# heater_control.net
KiCad netlist of a schematic drawn in Altium Designer
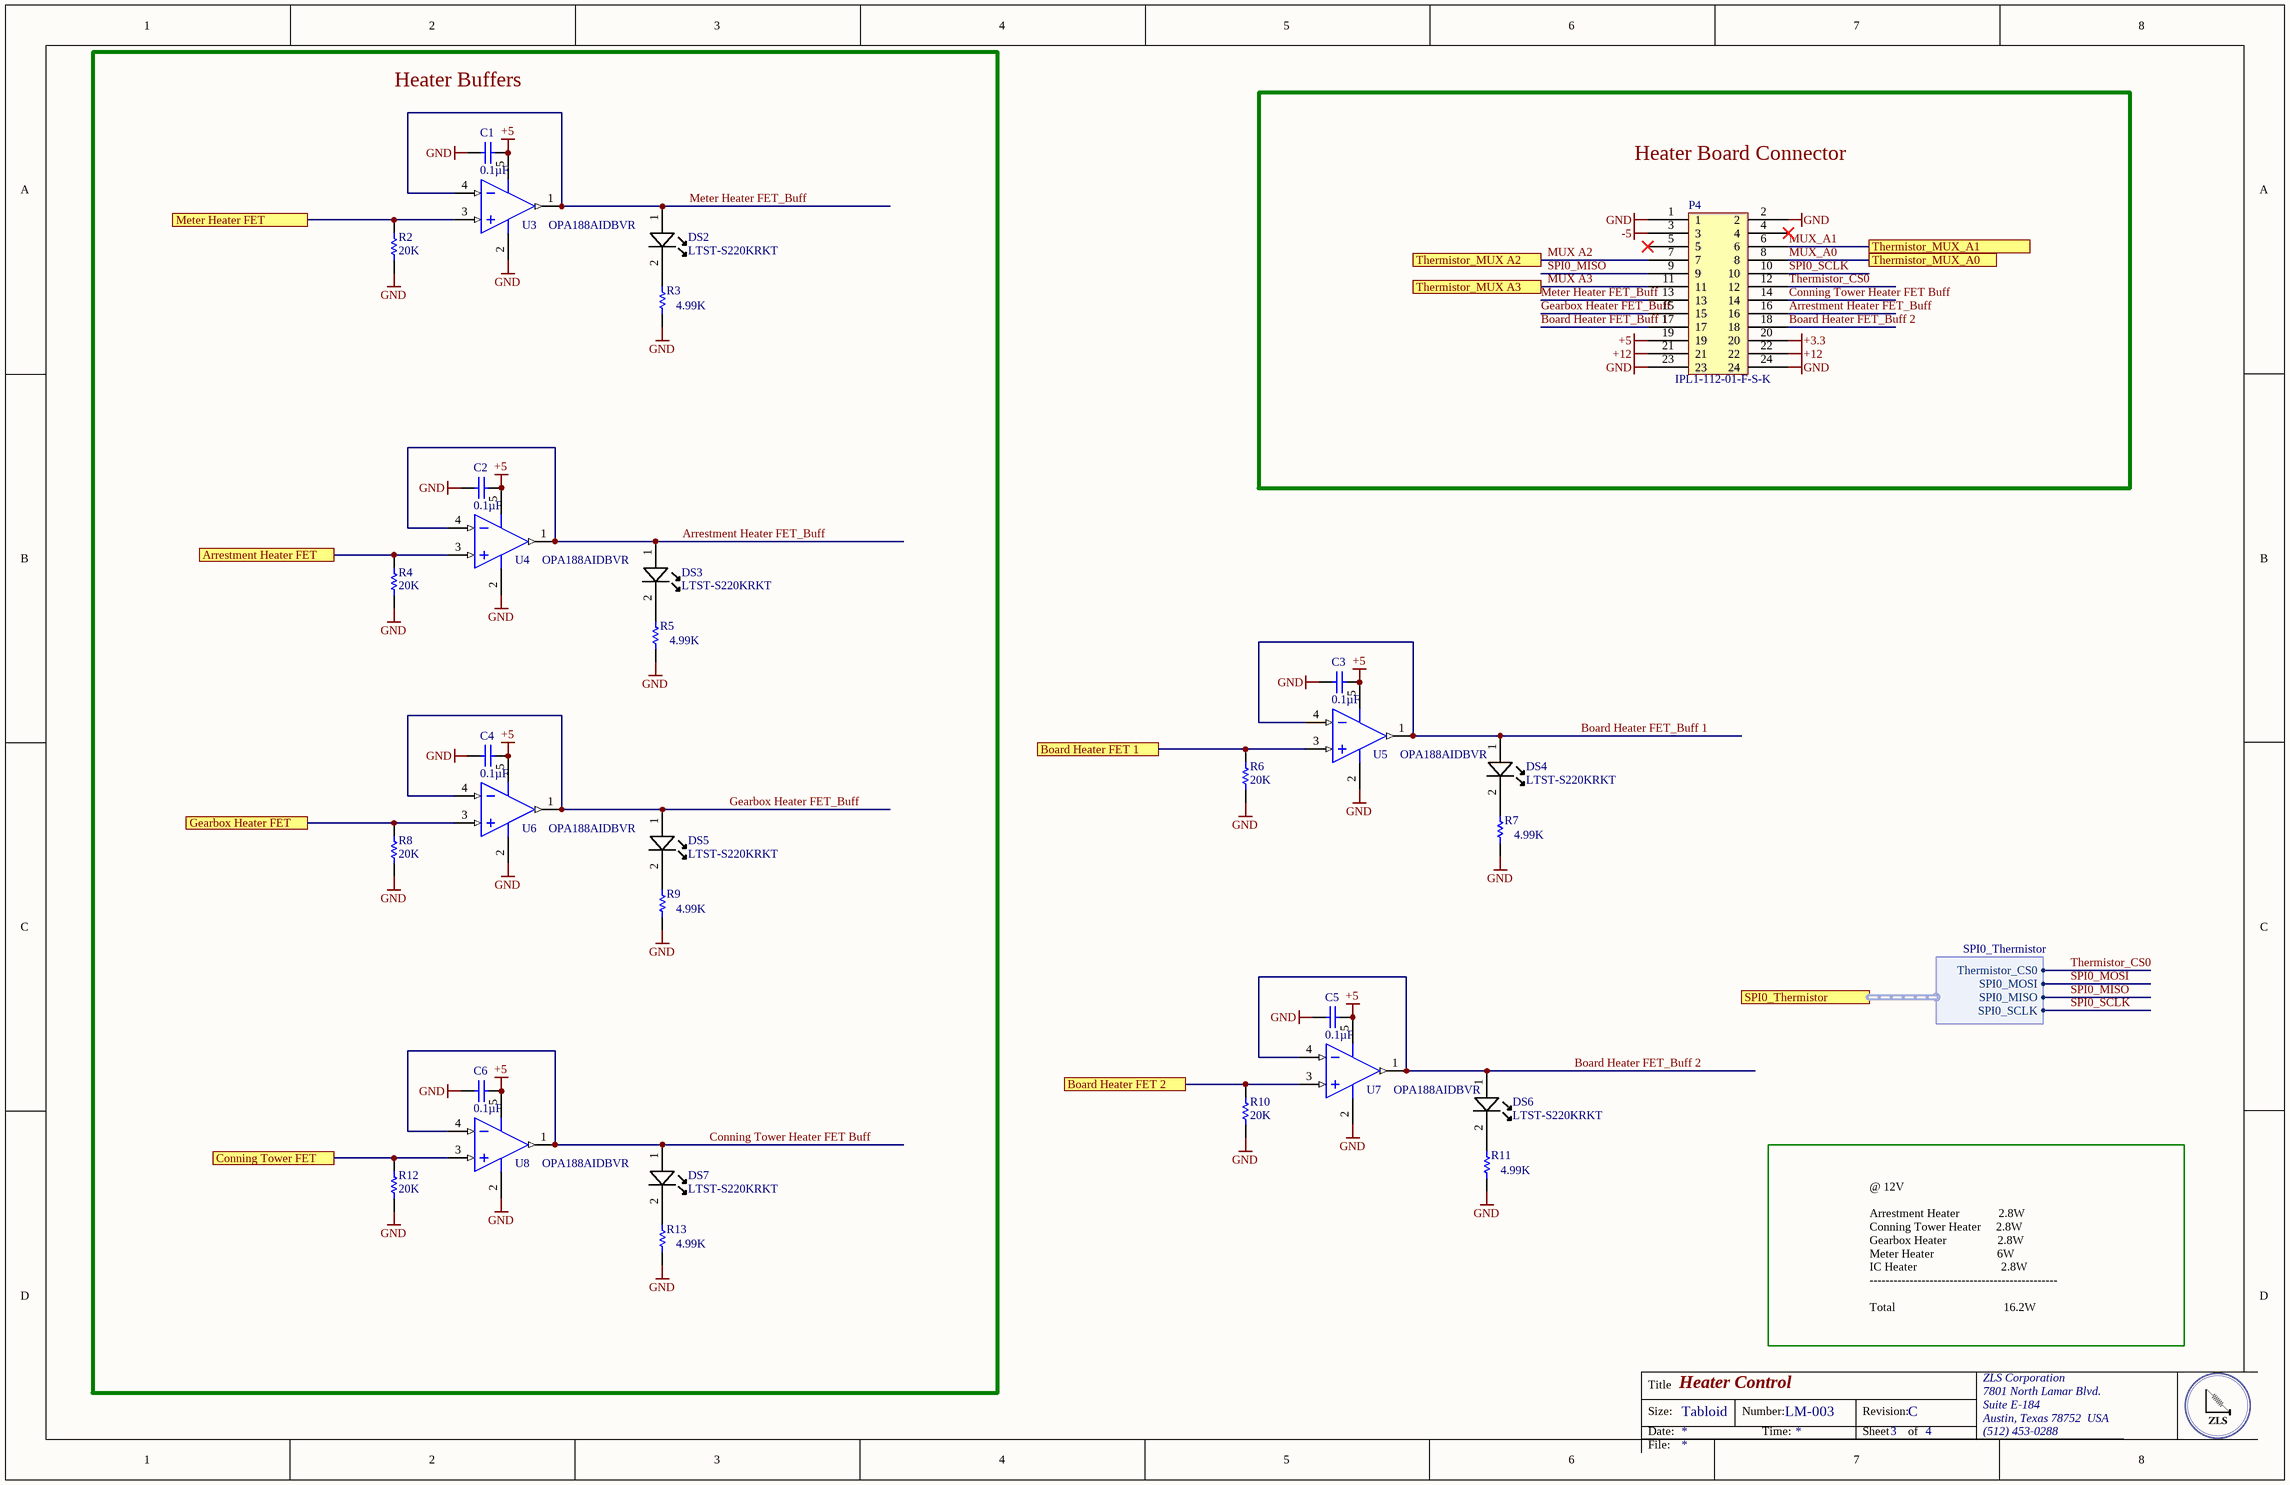
[diagram p0: heater_control.SchDoc]

(export (version "E")
  (design (tool "Eeschema 10.0.6"))
  (components
    (comp (ref "C1")
      (value "CAP CER 0.1UF 25V X7R 0805")
      (footprint "CAPC0805(2012)145_N")
      (fields
        (field (name "MANUFACTURER") "Murata Electronics North America")
        (field (name "MANUFACTURER PART NUMBER") "GRM21BR71E104KA01L")
        (field (name "CAPACITANCE") "0.1µF")
        (field (name "TOLERANCE") "±10%")
      )
      (libsource (lib "Altium Content Vault") (part "CMP-1036-04795-1"))
    )
    (comp (ref "C2")
      (value "CAP CER 0.1UF 25V X7R 0805")
      (footprint "CAPC0805(2012)145_N")
      (fields
        (field (name "MANUFACTURER") "Murata Electronics North America")
        (field (name "MANUFACTURER PART NUMBER") "GRM21BR71E104KA01L")
        (field (name "CAPACITANCE") "0.1µF")
        (field (name "TOLERANCE") "±10%")
      )
      (libsource (lib "Altium Content Vault") (part "CMP-1036-04795-1"))
    )
    (comp (ref "C3")
      (value "CAP CER 0.1UF 25V X7R 0805")
      (footprint "CAPC0805(2012)145_N")
      (fields
        (field (name "MANUFACTURER") "Murata Electronics North America")
        (field (name "MANUFACTURER PART NUMBER") "GRM21BR71E104KA01L")
        (field (name "CAPACITANCE") "0.1µF")
        (field (name "TOLERANCE") "±10%")
      )
      (libsource (lib "Altium Content Vault") (part "CMP-1036-04795-1"))
    )
    (comp (ref "C4")
      (value "CAP CER 0.1UF 25V X7R 0805")
      (footprint "CAPC0805(2012)145_N")
      (fields
        (field (name "MANUFACTURER") "Murata Electronics North America")
        (field (name "MANUFACTURER PART NUMBER") "GRM21BR71E104KA01L")
        (field (name "CAPACITANCE") "0.1µF")
        (field (name "TOLERANCE") "±10%")
      )
      (libsource (lib "Altium Content Vault") (part "CMP-1036-04795-1"))
    )
    (comp (ref "C5")
      (value "CAP CER 0.1UF 25V X7R 0805")
      (footprint "CAPC0805(2012)145_N")
      (fields
        (field (name "MANUFACTURER") "Murata Electronics North America")
        (field (name "MANUFACTURER PART NUMBER") "GRM21BR71E104KA01L")
        (field (name "CAPACITANCE") "0.1µF")
        (field (name "TOLERANCE") "±10%")
      )
      (libsource (lib "Altium Content Vault") (part "CMP-1036-04795-1"))
    )
    (comp (ref "C6")
      (value "CAP CER 0.1UF 25V X7R 0805")
      (footprint "CAPC0805(2012)145_N")
      (fields
        (field (name "MANUFACTURER") "Murata Electronics North America")
        (field (name "MANUFACTURER PART NUMBER") "GRM21BR71E104KA01L")
        (field (name "CAPACITANCE") "0.1µF")
        (field (name "TOLERANCE") "±10%")
      )
      (libsource (lib "Altium Content Vault") (part "CMP-1036-04795-1"))
    )
    (comp (ref "DS2")
      (value "Visible Name Value Type    False Description Lite-On LTST-S220KRKT Red LED, 631 nm 2012 (0805) Side View, Rectangle Lens SMD package STRING")
      (footprint "0805C_L")
      (fields
        (field (name "MANUFACTURER") "Vishay / Lite-On")
        (field (name "MANUFACTURER PART NUMBER") "LTST-S220KRKT")
      )
      (libsource (lib "*") (part "LED A/K"))
    )
    (comp (ref "DS3")
      (value "Visible Name Value Type    False Description Lite-On LTST-S220KRKT Red LED, 631 nm 2012 (0805) Side View, Rectangle Lens SMD package STRING")
      (footprint "0805C_L")
      (fields
        (field (name "MANUFACTURER") "Vishay / Lite-On")
        (field (name "MANUFACTURER PART NUMBER") "LTST-S220KRKT")
      )
      (libsource (lib "*") (part "LED A/K"))
    )
    (comp (ref "DS4")
      (value "Visible Name Value Type    False Description Lite-On LTST-S220KRKT Red LED, 631 nm 2012 (0805) Side View, Rectangle Lens SMD package STRING")
      (footprint "0805C_L")
      (fields
        (field (name "MANUFACTURER") "Vishay / Lite-On")
        (field (name "MANUFACTURER PART NUMBER") "LTST-S220KRKT")
      )
      (libsource (lib "*") (part "LED A/K"))
    )
    (comp (ref "DS5")
      (value "Visible Name Value Type    False Description Lite-On LTST-S220KRKT Red LED, 631 nm 2012 (0805) Side View, Rectangle Lens SMD package STRING")
      (footprint "0805C_L")
      (fields
        (field (name "MANUFACTURER") "Vishay / Lite-On")
        (field (name "MANUFACTURER PART NUMBER") "LTST-S220KRKT")
      )
      (libsource (lib "*") (part "LED A/K"))
    )
    (comp (ref "DS6")
      (value "Visible Name Value Type    False Description Lite-On LTST-S220KRKT Red LED, 631 nm 2012 (0805) Side View, Rectangle Lens SMD package STRING")
      (footprint "0805C_L")
      (fields
        (field (name "MANUFACTURER") "Vishay / Lite-On")
        (field (name "MANUFACTURER PART NUMBER") "LTST-S220KRKT")
      )
      (libsource (lib "*") (part "LED A/K"))
    )
    (comp (ref "DS7")
      (value "Visible Name Value Type    False Description Lite-On LTST-S220KRKT Red LED, 631 nm 2012 (0805) Side View, Rectangle Lens SMD package STRING")
      (footprint "0805C_L")
      (fields
        (field (name "MANUFACTURER") "Vishay / Lite-On")
        (field (name "MANUFACTURER PART NUMBER") "LTST-S220KRKT")
      )
      (libsource (lib "*") (part "LED A/K"))
    )
    (comp (ref "P4")
      (value "IPL1-112-01-F-S-K")
      (footprint "IPL1-112-01-F-S-K")
      (description "IPL1-112-01-F-D-K")
      (fields (field (name "MANUFACTURER") "Samtec Inc."))
      (libsource (lib "ZLS_Schematic_lib") (part "IPL1-112-01-F-S-K"))
    )
    (comp (ref "R2")
      (value "20K")
      (footprint "RESC0805(2012)_L")
      (description "RES SMD 20K OHM 1% 1/8W 0805")
      (fields
        (field (name "MANUFACTURER") "Panasonic Electronic Components")
        (field (name "MANUFACTURER PART NUMBER") "ERJ-6ENF2002V")
      )
      (libsource (lib "Altium Content Vault") (part "CMP-1013-00215-1"))
    )
    (comp (ref "R3")
      (value "4.99K")
      (footprint "RESC0805(2012)_L")
      (description "RES SMD 4.99K OHM 1% 1/8W 0805")
      (fields
        (field (name "MANUFACTURER") "Panasonic Electronic Components")
        (field (name "MANUFACTURER PART NUMBER") "ERJ-6ENF4991V")
      )
      (libsource (lib "Altium Content Vault") (part "CMP-1013-00215-1"))
    )
    (comp (ref "R4")
      (value "20K")
      (footprint "RESC0805(2012)_L")
      (description "RES SMD 20K OHM 1% 1/8W 0805")
      (fields
        (field (name "MANUFACTURER") "Panasonic Electronic Components")
        (field (name "MANUFACTURER PART NUMBER") "ERJ-6ENF2002V")
      )
      (libsource (lib "Altium Content Vault") (part "CMP-1013-00215-1"))
    )
    (comp (ref "R5")
      (value "4.99K")
      (footprint "RESC0805(2012)_L")
      (description "RES SMD 4.99K OHM 1% 1/8W 0805")
      (fields
        (field (name "MANUFACTURER") "Panasonic Electronic Components")
        (field (name "MANUFACTURER PART NUMBER") "ERJ-6ENF4991V")
      )
      (libsource (lib "Altium Content Vault") (part "CMP-1013-00215-1"))
    )
    (comp (ref "R6")
      (value "20K")
      (footprint "RESC0805(2012)_L")
      (description "RES SMD 20K OHM 1% 1/8W 0805")
      (fields
        (field (name "MANUFACTURER") "Panasonic Electronic Components")
        (field (name "MANUFACTURER PART NUMBER") "ERJ-6ENF2002V")
      )
      (libsource (lib "Altium Content Vault") (part "CMP-1013-00215-1"))
    )
    (comp (ref "R7")
      (value "4.99K")
      (footprint "RESC0805(2012)_L")
      (description "RES SMD 4.99K OHM 1% 1/8W 0805")
      (fields
        (field (name "MANUFACTURER") "Panasonic Electronic Components")
        (field (name "MANUFACTURER PART NUMBER") "ERJ-6ENF4991V")
      )
      (libsource (lib "Altium Content Vault") (part "CMP-1013-00215-1"))
    )
    (comp (ref "R8")
      (value "20K")
      (footprint "RESC0805(2012)_L")
      (description "RES SMD 20K OHM 1% 1/8W 0805")
      (fields
        (field (name "MANUFACTURER") "Panasonic Electronic Components")
        (field (name "MANUFACTURER PART NUMBER") "ERJ-6ENF2002V")
      )
      (libsource (lib "Altium Content Vault") (part "CMP-1013-00215-1"))
    )
    (comp (ref "R9")
      (value "4.99K")
      (footprint "RESC0805(2012)_L")
      (description "RES SMD 4.99K OHM 1% 1/8W 0805")
      (fields
        (field (name "MANUFACTURER") "Panasonic Electronic Components")
        (field (name "MANUFACTURER PART NUMBER") "ERJ-6ENF4991V")
      )
      (libsource (lib "Altium Content Vault") (part "CMP-1013-00215-1"))
    )
    (comp (ref "R10")
      (value "20K")
      (footprint "RESC0805(2012)_L")
      (description "RES SMD 20K OHM 1% 1/8W 0805")
      (fields
        (field (name "MANUFACTURER") "Panasonic Electronic Components")
        (field (name "MANUFACTURER PART NUMBER") "ERJ-6ENF2002V")
      )
      (libsource (lib "Altium Content Vault") (part "CMP-1013-00215-1"))
    )
    (comp (ref "R11")
      (value "4.99K")
      (footprint "RESC0805(2012)_L")
      (description "RES SMD 4.99K OHM 1% 1/8W 0805")
      (fields
        (field (name "MANUFACTURER") "Panasonic Electronic Components")
        (field (name "MANUFACTURER PART NUMBER") "ERJ-6ENF4991V")
      )
      (libsource (lib "Altium Content Vault") (part "CMP-1013-00215-1"))
    )
    (comp (ref "R12")
      (value "20K")
      (footprint "RESC0805(2012)_L")
      (description "RES SMD 20K OHM 1% 1/8W 0805")
      (fields
        (field (name "MANUFACTURER") "Panasonic Electronic Components")
        (field (name "MANUFACTURER PART NUMBER") "ERJ-6ENF2002V")
      )
      (libsource (lib "Altium Content Vault") (part "CMP-1013-00215-1"))
    )
    (comp (ref "R13")
      (value "4.99K")
      (footprint "RESC0805(2012)_L")
      (description "RES SMD 4.99K OHM 1% 1/8W 0805")
      (fields
        (field (name "MANUFACTURER") "Panasonic Electronic Components")
        (field (name "MANUFACTURER PART NUMBER") "ERJ-6ENF4991V")
      )
      (libsource (lib "Altium Content Vault") (part "CMP-1013-00215-1"))
    )
    (comp (ref "U3")
      (value "OPA188AIDBVR")
      (footprint "DBV0005A_M")
      (fields (field (name "MANUFACTURER") "Texas Instruments"))
      (libsource (lib "Altium Content Vault") (part "CMP-0809-00005-2"))
    )
    (comp (ref "U4")
      (value "OPA188AIDBVR")
      (footprint "DBV0005A_M")
      (fields (field (name "MANUFACTURER") "Texas Instruments"))
      (libsource (lib "Altium Content Vault") (part "CMP-0809-00005-2"))
    )
    (comp (ref "U5")
      (value "OPA188AIDBVR")
      (footprint "DBV0005A_M")
      (fields (field (name "MANUFACTURER") "Texas Instruments"))
      (libsource (lib "Altium Content Vault") (part "CMP-0809-00005-2"))
    )
    (comp (ref "U6")
      (value "OPA188AIDBVR")
      (footprint "DBV0005A_M")
      (fields (field (name "MANUFACTURER") "Texas Instruments"))
      (libsource (lib "Altium Content Vault") (part "CMP-0809-00005-2"))
    )
    (comp (ref "U7")
      (value "OPA188AIDBVR")
      (footprint "DBV0005A_M")
      (fields (field (name "MANUFACTURER") "Texas Instruments"))
      (libsource (lib "Altium Content Vault") (part "CMP-0809-00005-2"))
    )
    (comp (ref "U8")
      (value "OPA188AIDBVR")
      (footprint "DBV0005A_M")
      (fields (field (name "MANUFACTURER") "Texas Instruments"))
      (libsource (lib "Altium Content Vault") (part "CMP-0809-00005-2"))
    )
  )
  (nets
    (net (code "2") (name "+3.3") (class "Default")
      (node (ref "P4") (pin "20") (pinfunction "20_20") (pintype "passive"))
    )
    (net (code "3") (name "+5") (class "Default")
      (node (ref "C1") (pin "2") (pinfunction "2_2") (pintype "passive"))
      (node (ref "C2") (pin "2") (pinfunction "2_2") (pintype "passive"))
      (node (ref "C3") (pin "2") (pinfunction "2_2") (pintype "passive"))
      (node (ref "C4") (pin "2") (pinfunction "2_2") (pintype "passive"))
      (node (ref "C5") (pin "2") (pinfunction "2_2") (pintype "passive"))
      (node (ref "C6") (pin "2") (pinfunction "2_2") (pintype "passive"))
      (node (ref "P4") (pin "19") (pinfunction "19_19") (pintype "passive"))
      (node (ref "U3") (pin "5") (pinfunction "V+_5") (pintype "power_in"))
      (node (ref "U4") (pin "5") (pinfunction "V+_5") (pintype "power_in"))
      (node (ref "U5") (pin "5") (pinfunction "V+_5") (pintype "power_in"))
      (node (ref "U6") (pin "5") (pinfunction "V+_5") (pintype "power_in"))
      (node (ref "U7") (pin "5") (pinfunction "V+_5") (pintype "power_in"))
      (node (ref "U8") (pin "5") (pinfunction "V+_5") (pintype "power_in"))
    )
    (net (code "4") (name "+12") (class "Default")
      (node (ref "P4") (pin "21") (pinfunction "21_21") (pintype "passive"))
      (node (ref "P4") (pin "22") (pinfunction "22_22") (pintype "passive"))
    )
    (net (code "5") (name "-5") (class "Default")
      (node (ref "P4") (pin "3") (pinfunction "3_3") (pintype "passive"))
    )
    (net (code "6") (name "/Arrestment Heater FET") (class "Default")
      (node (ref "R4") (pin "1") (pinfunction "1_1") (pintype "passive"))
      (node (ref "U4") (pin "3") (pinfunction "IN+_3") (pintype "input"))
    )
    (net (code "7") (name "/Arrestment Heater FET_Buff") (class "Default")
      (node (ref "DS3") (pin "1") (pinfunction "A_1") (pintype "passive"))
      (node (ref "P4") (pin "16") (pinfunction "16_16") (pintype "passive"))
      (node (ref "U4") (pin "1") (pinfunction "OUT_1") (pintype "output"))
      (node (ref "U4") (pin "4") (pinfunction "IN-_4") (pintype "input"))
    )
    (net (code "8") (name "/Board Heater FET 1") (class "Default")
      (node (ref "R6") (pin "1") (pinfunction "1_1") (pintype "passive"))
      (node (ref "U5") (pin "3") (pinfunction "IN+_3") (pintype "input"))
    )
    (net (code "9") (name "/Board Heater FET 2") (class "Default")
      (node (ref "R10") (pin "1") (pinfunction "1_1") (pintype "passive"))
      (node (ref "U7") (pin "3") (pinfunction "IN+_3") (pintype "input"))
    )
    (net (code "10") (name "/Board Heater FET_Buff 1") (class "Default")
      (node (ref "DS4") (pin "1") (pinfunction "A_1") (pintype "passive"))
      (node (ref "P4") (pin "17") (pinfunction "17_17") (pintype "passive"))
      (node (ref "U5") (pin "1") (pinfunction "OUT_1") (pintype "output"))
      (node (ref "U5") (pin "4") (pinfunction "IN-_4") (pintype "input"))
    )
    (net (code "11") (name "/Board Heater FET_Buff 2") (class "Default")
      (node (ref "DS6") (pin "1") (pinfunction "A_1") (pintype "passive"))
      (node (ref "P4") (pin "18") (pinfunction "18_18") (pintype "passive"))
      (node (ref "U7") (pin "1") (pinfunction "OUT_1") (pintype "output"))
      (node (ref "U7") (pin "4") (pinfunction "IN-_4") (pintype "input"))
    )
    (net (code "12") (name "/Conning Tower FET") (class "Default")
      (node (ref "R12") (pin "1") (pinfunction "1_1") (pintype "passive"))
      (node (ref "U8") (pin "3") (pinfunction "IN+_3") (pintype "input"))
    )
    (net (code "13") (name "/Conning Tower Heater FET Buff") (class "Default")
      (node (ref "DS7") (pin "1") (pinfunction "A_1") (pintype "passive"))
      (node (ref "P4") (pin "14") (pinfunction "14_14") (pintype "passive"))
      (node (ref "U8") (pin "1") (pinfunction "OUT_1") (pintype "output"))
      (node (ref "U8") (pin "4") (pinfunction "IN-_4") (pintype "input"))
    )
    (net (code "14") (name "/Gearbox Heater FET") (class "Default")
      (node (ref "R8") (pin "1") (pinfunction "1_1") (pintype "passive"))
      (node (ref "U6") (pin "3") (pinfunction "IN+_3") (pintype "input"))
    )
    (net (code "15") (name "/Gearbox Heater FET_Buff") (class "Default")
      (node (ref "DS5") (pin "1") (pinfunction "A_1") (pintype "passive"))
      (node (ref "P4") (pin "15") (pinfunction "15_15") (pintype "passive"))
      (node (ref "U6") (pin "1") (pinfunction "OUT_1") (pintype "output"))
      (node (ref "U6") (pin "4") (pinfunction "IN-_4") (pintype "input"))
    )
    (net (code "16") (name "/MUX A2") (class "Default")
      (node (ref "P4") (pin "7") (pinfunction "7_7") (pintype "passive"))
    )
    (net (code "17") (name "/MUX A3") (class "Default")
      (node (ref "P4") (pin "11") (pinfunction "11_11") (pintype "passive"))
    )
    (net (code "18") (name "/MUX_A0") (class "Default")
      (node (ref "P4") (pin "8") (pinfunction "8_8") (pintype "passive"))
    )
    (net (code "19") (name "/MUX_A1") (class "Default")
      (node (ref "P4") (pin "6") (pinfunction "6_6") (pintype "passive"))
    )
    (net (code "20") (name "/Meter Heater FET") (class "Default")
      (node (ref "R2") (pin "1") (pinfunction "1_1") (pintype "passive"))
      (node (ref "U3") (pin "3") (pinfunction "IN+_3") (pintype "input"))
    )
    (net (code "21") (name "/Meter Heater FET_Buff") (class "Default")
      (node (ref "DS2") (pin "1") (pinfunction "A_1") (pintype "passive"))
      (node (ref "P4") (pin "13") (pinfunction "13_13") (pintype "passive"))
      (node (ref "U3") (pin "1") (pinfunction "OUT_1") (pintype "output"))
      (node (ref "U3") (pin "4") (pinfunction "IN-_4") (pintype "input"))
    )
    (net (code "22") (name "/SPI0_MISO") (class "Default")
      (node (ref "P4") (pin "9") (pinfunction "9_9") (pintype "passive"))
    )
    (net (code "24") (name "/SPI0_SCLK") (class "Default")
      (node (ref "P4") (pin "10") (pinfunction "10_10") (pintype "passive"))
    )
    (net (code "25") (name "/Thermistor_CS0") (class "Default")
      (node (ref "P4") (pin "12") (pinfunction "12_12") (pintype "passive"))
    )
    (net (code "27") (name "GND") (class "Default")
      (node (ref "C1") (pin "1") (pinfunction "1_1") (pintype "passive"))
      (node (ref "C2") (pin "1") (pinfunction "1_1") (pintype "passive"))
      (node (ref "C3") (pin "1") (pinfunction "1_1") (pintype "passive"))
      (node (ref "C4") (pin "1") (pinfunction "1_1") (pintype "passive"))
      (node (ref "C5") (pin "1") (pinfunction "1_1") (pintype "passive"))
      (node (ref "C6") (pin "1") (pinfunction "1_1") (pintype "passive"))
      (node (ref "P4") (pin "1") (pinfunction "1_1") (pintype "passive"))
      (node (ref "P4") (pin "2") (pinfunction "2_2") (pintype "passive"))
      (node (ref "P4") (pin "23") (pinfunction "23_23") (pintype "passive"))
      (node (ref "P4") (pin "24") (pinfunction "24_24") (pintype "passive"))
      (node (ref "R10") (pin "2") (pinfunction "2_2") (pintype "passive"))
      (node (ref "R11") (pin "2") (pinfunction "2_2") (pintype "passive"))
      (node (ref "R12") (pin "2") (pinfunction "2_2") (pintype "passive"))
      (node (ref "R13") (pin "2") (pinfunction "2_2") (pintype "passive"))
      (node (ref "R2") (pin "2") (pinfunction "2_2") (pintype "passive"))
      (node (ref "R3") (pin "2") (pinfunction "2_2") (pintype "passive"))
      (node (ref "R4") (pin "2") (pinfunction "2_2") (pintype "passive"))
      (node (ref "R5") (pin "2") (pinfunction "2_2") (pintype "passive"))
      (node (ref "R6") (pin "2") (pinfunction "2_2") (pintype "passive"))
      (node (ref "R7") (pin "2") (pinfunction "2_2") (pintype "passive"))
      (node (ref "R8") (pin "2") (pinfunction "2_2") (pintype "passive"))
      (node (ref "R9") (pin "2") (pinfunction "2_2") (pintype "passive"))
      (node (ref "U3") (pin "2") (pinfunction "V-_2") (pintype "power_in"))
      (node (ref "U4") (pin "2") (pinfunction "V-_2") (pintype "power_in"))
      (node (ref "U5") (pin "2") (pinfunction "V-_2") (pintype "power_in"))
      (node (ref "U6") (pin "2") (pinfunction "V-_2") (pintype "power_in"))
      (node (ref "U7") (pin "2") (pinfunction "V-_2") (pintype "power_in"))
      (node (ref "U8") (pin "2") (pinfunction "V-_2") (pintype "power_in"))
    )
    (net (code "28") (name "Net-(DS2-K)") (class "Default")
      (node (ref "DS2") (pin "2") (pinfunction "K_2") (pintype "passive"))
      (node (ref "R3") (pin "1") (pinfunction "1_1") (pintype "passive"))
    )
    (net (code "29") (name "Net-(DS3-K)") (class "Default")
      (node (ref "DS3") (pin "2") (pinfunction "K_2") (pintype "passive"))
      (node (ref "R5") (pin "1") (pinfunction "1_1") (pintype "passive"))
    )
    (net (code "30") (name "Net-(DS4-K)") (class "Default")
      (node (ref "DS4") (pin "2") (pinfunction "K_2") (pintype "passive"))
      (node (ref "R7") (pin "1") (pinfunction "1_1") (pintype "passive"))
    )
    (net (code "31") (name "Net-(DS5-K)") (class "Default")
      (node (ref "DS5") (pin "2") (pinfunction "K_2") (pintype "passive"))
      (node (ref "R9") (pin "1") (pinfunction "1_1") (pintype "passive"))
    )
    (net (code "32") (name "Net-(DS6-K)") (class "Default")
      (node (ref "DS6") (pin "2") (pinfunction "K_2") (pintype "passive"))
      (node (ref "R11") (pin "1") (pinfunction "1_1") (pintype "passive"))
    )
    (net (code "33") (name "Net-(DS7-K)") (class "Default")
      (node (ref "DS7") (pin "2") (pinfunction "K_2") (pintype "passive"))
      (node (ref "R13") (pin "1") (pinfunction "1_1") (pintype "passive"))
    )
    (net (code "34") (name "unconnected-(P4-Pad4)") (class "Default")
      (node (ref "P4") (pin "4") (pinfunction "4_4") (pintype "passive+no_connect"))
    )
    (net (code "35") (name "unconnected-(P4-Pad5)") (class "Default")
      (node (ref "P4") (pin "5") (pinfunction "5_5") (pintype "passive+no_connect"))
    )
  )
)
